# ft232h.net
KiCad netlist of a schematic drawn in Altium Designer
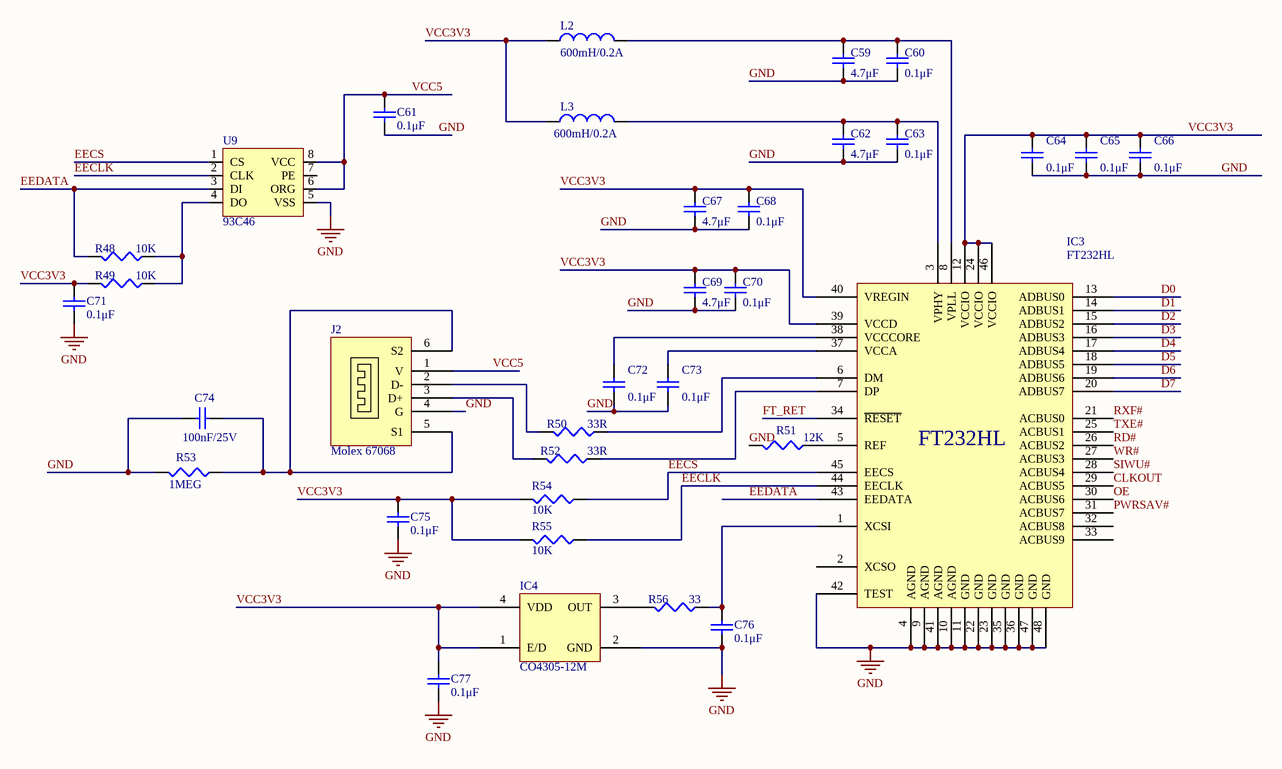
[diagram p0: ft232h.SchDoc]

(export (version "E")
  (design (tool "Eeschema 10.0.6"))
  (components
    (comp (ref "C59")
      (value "4.7μF")
      (footprint "1608[0603]")
      (description "Capacitor (Semiconductor SIM Model)")
      (fields (field (name "Comment") "Cap Semi") (field (name "PUBLISHER") "Altium Limited"))
      (libsource (lib "Miscellaneous Devices") (part "Cap Semi"))
    )
    (comp (ref "C60")
      (value "0.1μF")
      (footprint "1608[0603]")
      (description "Capacitor (Semiconductor SIM Model)")
      (fields (field (name "Comment") "Cap Semi") (field (name "PUBLISHER") "Altium Limited"))
      (libsource (lib "Miscellaneous Devices") (part "Cap Semi"))
    )
    (comp (ref "C61")
      (value "0.1μF")
      (footprint "1608[0603]")
      (description "Capacitor (Semiconductor SIM Model)")
      (fields (field (name "Comment") "Cap Semi") (field (name "PUBLISHER") "Altium Limited"))
      (libsource (lib "Miscellaneous Devices") (part "Cap Semi"))
    )
    (comp (ref "C62")
      (value "4.7μF")
      (footprint "1608[0603]")
      (description "Capacitor (Semiconductor SIM Model)")
      (fields (field (name "Comment") "Cap Semi") (field (name "PUBLISHER") "Altium Limited"))
      (libsource (lib "Miscellaneous Devices") (part "Cap Semi"))
    )
    (comp (ref "C63")
      (value "0.1μF")
      (footprint "1608[0603]")
      (description "Capacitor (Semiconductor SIM Model)")
      (fields (field (name "Comment") "Cap Semi") (field (name "PUBLISHER") "Altium Limited"))
      (libsource (lib "Miscellaneous Devices") (part "Cap Semi"))
    )
    (comp (ref "C64")
      (value "0.1μF")
      (footprint "1608[0603]")
      (description "Capacitor (Semiconductor SIM Model)")
      (fields (field (name "Comment") "Cap Semi") (field (name "PUBLISHER") "Altium Limited"))
      (libsource (lib "Miscellaneous Devices") (part "Cap Semi"))
    )
    (comp (ref "C65")
      (value "0.1μF")
      (footprint "1608[0603]")
      (description "Capacitor (Semiconductor SIM Model)")
      (fields (field (name "Comment") "Cap Semi") (field (name "PUBLISHER") "Altium Limited"))
      (libsource (lib "Miscellaneous Devices") (part "Cap Semi"))
    )
    (comp (ref "C66")
      (value "0.1μF")
      (footprint "1608[0603]")
      (description "Capacitor (Semiconductor SIM Model)")
      (fields (field (name "Comment") "Cap Semi") (field (name "PUBLISHER") "Altium Limited"))
      (libsource (lib "Miscellaneous Devices") (part "Cap Semi"))
    )
    (comp (ref "C67")
      (value "4.7μF")
      (footprint "1608[0603]")
      (description "Capacitor (Semiconductor SIM Model)")
      (fields (field (name "Comment") "Cap Semi") (field (name "PUBLISHER") "Altium Limited"))
      (libsource (lib "Miscellaneous Devices") (part "Cap Semi"))
    )
    (comp (ref "C68")
      (value "0.1μF")
      (footprint "1608[0603]")
      (description "Capacitor (Semiconductor SIM Model)")
      (fields (field (name "Comment") "Cap Semi") (field (name "PUBLISHER") "Altium Limited"))
      (libsource (lib "Miscellaneous Devices") (part "Cap Semi"))
    )
    (comp (ref "C69")
      (value "4.7μF")
      (footprint "1608[0603]")
      (description "Capacitor (Semiconductor SIM Model)")
      (fields (field (name "Comment") "Cap Semi") (field (name "PUBLISHER") "Altium Limited"))
      (libsource (lib "Miscellaneous Devices") (part "Cap Semi"))
    )
    (comp (ref "C70")
      (value "0.1μF")
      (footprint "1608[0603]")
      (description "Capacitor (Semiconductor SIM Model)")
      (fields (field (name "Comment") "Cap Semi") (field (name "PUBLISHER") "Altium Limited"))
      (libsource (lib "Miscellaneous Devices") (part "Cap Semi"))
    )
    (comp (ref "C71")
      (value "0.1μF")
      (footprint "1608[0603]")
      (description "Capacitor (Semiconductor SIM Model)")
      (fields (field (name "Comment") "Cap Semi") (field (name "PUBLISHER") "Altium Limited"))
      (libsource (lib "Miscellaneous Devices") (part "Cap Semi"))
    )
    (comp (ref "C72")
      (value "0.1μF")
      (footprint "1608[0603]")
      (description "Capacitor (Semiconductor SIM Model)")
      (fields (field (name "Comment") "Cap Semi") (field (name "PUBLISHER") "Altium Limited"))
      (libsource (lib "Miscellaneous Devices") (part "Cap Semi"))
    )
    (comp (ref "C73")
      (value "0.1μF")
      (footprint "1608[0603]")
      (description "Capacitor (Semiconductor SIM Model)")
      (fields (field (name "Comment") "Cap Semi") (field (name "PUBLISHER") "Altium Limited"))
      (libsource (lib "Miscellaneous Devices") (part "Cap Semi"))
    )
    (comp (ref "C74")
      (value "100nF/25V")
      (footprint "1608[0603]")
      (description "Capacitor (Semiconductor SIM Model)")
      (fields (field (name "Comment") "Cap Semi") (field (name "PUBLISHER") "Altium Limited"))
      (libsource (lib "Miscellaneous Devices") (part "Cap Semi"))
    )
    (comp (ref "C75")
      (value "0.1μF")
      (footprint "1608[0603]")
      (description "Capacitor (Semiconductor SIM Model)")
      (fields (field (name "Comment") "Cap Semi") (field (name "PUBLISHER") "Altium Limited"))
      (libsource (lib "Miscellaneous Devices") (part "Cap Semi"))
    )
    (comp (ref "C76")
      (value "0.1μF")
      (footprint "1608[0603]")
      (description "Capacitor (Semiconductor SIM Model)")
      (fields (field (name "Comment") "Cap Semi") (field (name "PUBLISHER") "Altium Limited"))
      (libsource (lib "Miscellaneous Devices") (part "Cap Semi"))
    )
    (comp (ref "C77")
      (value "0.1μF")
      (footprint "1608[0603]")
      (description "Capacitor (Semiconductor SIM Model)")
      (fields (field (name "Comment") "Cap Semi") (field (name "PUBLISHER") "Altium Limited"))
      (libsource (lib "Miscellaneous Devices") (part "Cap Semi"))
    )
    (comp (ref "IC3")
      (value "FT232HL")
      (footprint "FTDI Footprints:LQFP-48_L")
      (libsource (lib "nir_usb") (part "FT232HL"))
    )
    (comp (ref "IC4")
      (value "CO4305-12M")
      (footprint "CO4305-12")
      (libsource (lib "nir_usb") (part "CO4305-12M"))
    )
    (comp (ref "J2")
      (value "Molex 67068")
      (footprint "USB-A")
      (libsource (lib "nir_usb") (part "Molex 67068"))
    )
    (comp (ref "L2")
      (value "600mH/0.2A")
      (footprint "0603")
      (description "Inductor")
      (fields (field (name "PUBLISHER") "Altium Limited"))
      (libsource (lib "Miscellaneous Devices") (part "Inductor"))
    )
    (comp (ref "L3")
      (value "600mH/0.2A")
      (footprint "0603")
      (description "Inductor")
      (fields (field (name "PUBLISHER") "Altium Limited"))
      (libsource (lib "Miscellaneous Devices") (part "Inductor"))
    )
    (comp (ref "R48")
      (value "10K")
      (footprint "J1-0603")
      (description "Resistor")
      (fields (field (name "Comment") "Res3") (field (name "PUBLISHER") "Altium Limited"))
      (libsource (lib "Miscellaneous Devices") (part "Res3"))
    )
    (comp (ref "R49")
      (value "10K")
      (footprint "J1-0603")
      (description "Resistor")
      (fields (field (name "Comment") "Res3") (field (name "PUBLISHER") "Altium Limited"))
      (libsource (lib "Miscellaneous Devices") (part "Res3"))
    )
    (comp (ref "R50")
      (value "33R")
      (footprint "J1-0603")
      (description "Resistor")
      (fields (field (name "Comment") "Res3") (field (name "PUBLISHER") "Altium Limited"))
      (libsource (lib "Miscellaneous Devices") (part "Res3"))
    )
    (comp (ref "R51")
      (value "12K")
      (footprint "J1-0603")
      (description "Resistor")
      (fields (field (name "Comment") "Res3") (field (name "PUBLISHER") "Altium Limited"))
      (libsource (lib "Miscellaneous Devices") (part "Res3"))
    )
    (comp (ref "R52")
      (value "33R")
      (footprint "J1-0603")
      (description "Resistor")
      (fields (field (name "Comment") "Res3") (field (name "PUBLISHER") "Altium Limited"))
      (libsource (lib "Miscellaneous Devices") (part "Res3"))
    )
    (comp (ref "R53")
      (value "1MEG")
      (footprint "J1-0603")
      (description "Resistor")
      (fields (field (name "Comment") "Res3") (field (name "PUBLISHER") "Altium Limited"))
      (libsource (lib "Miscellaneous Devices") (part "Res3"))
    )
    (comp (ref "R54")
      (value "10K")
      (footprint "J1-0603")
      (description "Resistor")
      (fields (field (name "Comment") "Res3") (field (name "PUBLISHER") "Altium Limited"))
      (libsource (lib "Miscellaneous Devices") (part "Res3"))
    )
    (comp (ref "R55")
      (value "10K")
      (footprint "J1-0603")
      (description "Resistor")
      (fields (field (name "Comment") "Res3") (field (name "PUBLISHER") "Altium Limited"))
      (libsource (lib "Miscellaneous Devices") (part "Res3"))
    )
    (comp (ref "R56")
      (value "33")
      (footprint "J1-0603")
      (description "Resistor")
      (fields (field (name "Comment") "Res3") (field (name "PUBLISHER") "Altium Limited"))
      (libsource (lib "Miscellaneous Devices") (part "Res3"))
    )
    (comp (ref "U9")
      (value "93C46")
      (footprint "SOIC127P600X175-8N")
      (libsource (lib "nir_usb") (part "93C46"))
    )
  )
  (nets
    (net (code "1") (name "/CLKOUT") (class "Default")
      (node (ref "IC3") (pin "29") (pinfunction "ACBUS5_29") (pintype "passive"))
    )
    (net (code "2") (name "/D0") (class "Default")
      (node (ref "IC3") (pin "13") (pinfunction "ADBUS0_13") (pintype "passive"))
    )
    (net (code "3") (name "/D1") (class "Default")
      (node (ref "IC3") (pin "14") (pinfunction "ADBUS1_14") (pintype "passive"))
    )
    (net (code "4") (name "/D2") (class "Default")
      (node (ref "IC3") (pin "15") (pinfunction "ADBUS2_15") (pintype "passive"))
    )
    (net (code "5") (name "/D3") (class "Default")
      (node (ref "IC3") (pin "16") (pinfunction "ADBUS3_16") (pintype "passive"))
    )
    (net (code "6") (name "/D4") (class "Default")
      (node (ref "IC3") (pin "17") (pinfunction "ADBUS4_17") (pintype "passive"))
    )
    (net (code "7") (name "/D5") (class "Default")
      (node (ref "IC3") (pin "18") (pinfunction "ADBUS5_18") (pintype "passive"))
    )
    (net (code "8") (name "/D6") (class "Default")
      (node (ref "IC3") (pin "19") (pinfunction "ADBUS6_19") (pintype "passive"))
    )
    (net (code "9") (name "/D7") (class "Default")
      (node (ref "IC3") (pin "20") (pinfunction "ADBUS7_20") (pintype "passive"))
    )
    (net (code "10") (name "/EECLK") (class "Default")
      (node (ref "IC3") (pin "44") (pinfunction "EECLK_44") (pintype "passive"))
      (node (ref "R55") (pin "1") (pinfunction "1_1") (pintype "passive"))
      (node (ref "U9") (pin "2") (pinfunction "CLK_2") (pintype "passive"))
    )
    (net (code "11") (name "/EECS") (class "Default")
      (node (ref "IC3") (pin "45") (pinfunction "EECS_45") (pintype "passive"))
      (node (ref "R54") (pin "1") (pinfunction "1_1") (pintype "passive"))
      (node (ref "U9") (pin "1") (pinfunction "CS_1") (pintype "passive"))
    )
    (net (code "12") (name "/EEDATA") (class "Default")
      (node (ref "IC3") (pin "43") (pinfunction "EEDATA_43") (pintype "passive"))
      (node (ref "R48") (pin "2") (pinfunction "2_2") (pintype "passive"))
      (node (ref "U9") (pin "3") (pinfunction "DI_3") (pintype "passive"))
    )
    (net (code "13") (name "/FT_RET") (class "Default")
      (node (ref "IC3") (pin "34") (pinfunction "~{RESET}_34") (pintype "passive"))
    )
    (net (code "14") (name "/OE") (class "Default")
      (node (ref "IC3") (pin "30") (pinfunction "ACBUS6_30") (pintype "passive"))
    )
    (net (code "15") (name "/PWRSAV#") (class "Default")
      (node (ref "IC3") (pin "31") (pinfunction "ACBUS7_31") (pintype "passive"))
    )
    (net (code "16") (name "/RD#") (class "Default")
      (node (ref "IC3") (pin "26") (pinfunction "ACBUS2_26") (pintype "passive"))
    )
    (net (code "17") (name "/RXF#") (class "Default")
      (node (ref "IC3") (pin "21") (pinfunction "ACBUS0_21") (pintype "passive"))
    )
    (net (code "18") (name "/SIWU#") (class "Default")
      (node (ref "IC3") (pin "28") (pinfunction "ACBUS4_28") (pintype "passive"))
    )
    (net (code "19") (name "/TXE#") (class "Default")
      (node (ref "IC3") (pin "25") (pinfunction "ACBUS1_25") (pintype "passive"))
    )
    (net (code "20") (name "/VCC3V3") (class "Default")
      (node (ref "C64") (pin "2") (pinfunction "2_2") (pintype "passive"))
      (node (ref "C65") (pin "2") (pinfunction "2_2") (pintype "passive"))
      (node (ref "C66") (pin "2") (pinfunction "2_2") (pintype "passive"))
      (node (ref "C67") (pin "2") (pinfunction "2_2") (pintype "passive"))
      (node (ref "C68") (pin "2") (pinfunction "2_2") (pintype "passive"))
      (node (ref "C69") (pin "2") (pinfunction "2_2") (pintype "passive"))
      (node (ref "C70") (pin "2") (pinfunction "2_2") (pintype "passive"))
      (node (ref "C71") (pin "2") (pinfunction "2_2") (pintype "passive"))
      (node (ref "C75") (pin "2") (pinfunction "2_2") (pintype "passive"))
      (node (ref "C77") (pin "2") (pinfunction "2_2") (pintype "passive"))
      (node (ref "IC3") (pin "12") (pinfunction "VCCIO_12") (pintype "passive"))
      (node (ref "IC3") (pin "24") (pinfunction "VCCIO_24") (pintype "passive"))
      (node (ref "IC3") (pin "39") (pinfunction "VCCD_39") (pintype "passive"))
      (node (ref "IC3") (pin "40") (pinfunction "VREGIN_40") (pintype "passive"))
      (node (ref "IC3") (pin "46") (pinfunction "VCCIO_46") (pintype "passive"))
      (node (ref "IC4") (pin "1") (pinfunction "E/D_1") (pintype "passive"))
      (node (ref "IC4") (pin "4") (pinfunction "VDD_4") (pintype "passive"))
      (node (ref "L2") (pin "1") (pinfunction "1_1") (pintype "passive"))
      (node (ref "L3") (pin "1") (pinfunction "1_1") (pintype "passive"))
      (node (ref "R49") (pin "2") (pinfunction "2_2") (pintype "passive"))
      (node (ref "R54") (pin "2") (pinfunction "2_2") (pintype "passive"))
      (node (ref "R55") (pin "2") (pinfunction "2_2") (pintype "passive"))
    )
    (net (code "21") (name "/VCC5") (class "Default")
      (node (ref "C61") (pin "2") (pinfunction "2_2") (pintype "passive"))
      (node (ref "J2") (pin "1") (pinfunction "V_1") (pintype "passive"))
      (node (ref "U9") (pin "6") (pinfunction "ORG_6") (pintype "passive"))
      (node (ref "U9") (pin "8") (pinfunction "VCC_8") (pintype "passive"))
    )
    (net (code "22") (name "/WR#") (class "Default")
      (node (ref "IC3") (pin "27") (pinfunction "ACBUS3_27") (pintype "passive"))
    )
    (net (code "23") (name "GND") (class "Default")
      (node (ref "C59") (pin "1") (pinfunction "1_1") (pintype "passive"))
      (node (ref "C60") (pin "1") (pinfunction "1_1") (pintype "passive"))
      (node (ref "C61") (pin "1") (pinfunction "1_1") (pintype "passive"))
      (node (ref "C62") (pin "1") (pinfunction "1_1") (pintype "passive"))
      (node (ref "C63") (pin "1") (pinfunction "1_1") (pintype "passive"))
      (node (ref "C64") (pin "1") (pinfunction "1_1") (pintype "passive"))
      (node (ref "C65") (pin "1") (pinfunction "1_1") (pintype "passive"))
      (node (ref "C66") (pin "1") (pinfunction "1_1") (pintype "passive"))
      (node (ref "C67") (pin "1") (pinfunction "1_1") (pintype "passive"))
      (node (ref "C68") (pin "1") (pinfunction "1_1") (pintype "passive"))
      (node (ref "C69") (pin "1") (pinfunction "1_1") (pintype "passive"))
      (node (ref "C70") (pin "1") (pinfunction "1_1") (pintype "passive"))
      (node (ref "C71") (pin "1") (pinfunction "1_1") (pintype "passive"))
      (node (ref "C72") (pin "1") (pinfunction "1_1") (pintype "passive"))
      (node (ref "C73") (pin "1") (pinfunction "1_1") (pintype "passive"))
      (node (ref "C74") (pin "1") (pinfunction "1_1") (pintype "passive"))
      (node (ref "C75") (pin "1") (pinfunction "1_1") (pintype "passive"))
      (node (ref "C76") (pin "1") (pinfunction "1_1") (pintype "passive"))
      (node (ref "C77") (pin "1") (pinfunction "1_1") (pintype "passive"))
      (node (ref "IC3") (pin "10") (pinfunction "AGND_10") (pintype "passive"))
      (node (ref "IC3") (pin "11") (pinfunction "GND_11") (pintype "passive"))
      (node (ref "IC3") (pin "22") (pinfunction "GND_22") (pintype "passive"))
      (node (ref "IC3") (pin "23") (pinfunction "GND_23") (pintype "passive"))
      (node (ref "IC3") (pin "35") (pinfunction "GND_35") (pintype "passive"))
      (node (ref "IC3") (pin "36") (pinfunction "GND_36") (pintype "passive"))
      (node (ref "IC3") (pin "4") (pinfunction "AGND_4") (pintype "passive"))
      (node (ref "IC3") (pin "41") (pinfunction "AGND_41") (pintype "passive"))
      (node (ref "IC3") (pin "42") (pinfunction "TEST_42") (pintype "passive"))
      (node (ref "IC3") (pin "47") (pinfunction "GND_47") (pintype "passive"))
      (node (ref "IC3") (pin "48") (pinfunction "GND_48") (pintype "passive"))
      (node (ref "IC3") (pin "9") (pinfunction "AGND_9") (pintype "passive"))
      (node (ref "IC4") (pin "2") (pinfunction "GND_2") (pintype "passive"))
      (node (ref "J2") (pin "4") (pinfunction "G_4") (pintype "passive"))
      (node (ref "R51") (pin "2") (pinfunction "2_2") (pintype "passive"))
      (node (ref "R53") (pin "2") (pinfunction "2_2") (pintype "passive"))
      (node (ref "U9") (pin "5") (pinfunction "VSS_5") (pintype "passive"))
    )
    (net (code "24") (name "Net-(IC3-DM)") (class "Default")
      (node (ref "IC3") (pin "6") (pinfunction "DM_6") (pintype "passive"))
      (node (ref "R50") (pin "1") (pinfunction "1_1") (pintype "passive"))
    )
    (net (code "25") (name "Net-(IC3-DP)") (class "Default")
      (node (ref "IC3") (pin "7") (pinfunction "DP_7") (pintype "passive"))
      (node (ref "R52") (pin "1") (pinfunction "1_1") (pintype "passive"))
    )
    (net (code "26") (name "Net-(IC3-REF)") (class "Default")
      (node (ref "IC3") (pin "5") (pinfunction "REF_5") (pintype "passive"))
      (node (ref "R51") (pin "1") (pinfunction "1_1") (pintype "passive"))
    )
    (net (code "27") (name "Net-(IC3-VCCA)") (class "Default")
      (node (ref "C73") (pin "2") (pinfunction "2_2") (pintype "passive"))
      (node (ref "IC3") (pin "37") (pinfunction "VCCA_37") (pintype "passive"))
    )
    (net (code "28") (name "Net-(IC3-VCCCORE)") (class "Default")
      (node (ref "C72") (pin "2") (pinfunction "2_2") (pintype "passive"))
      (node (ref "IC3") (pin "38") (pinfunction "VCCCORE_38") (pintype "passive"))
    )
    (net (code "29") (name "Net-(IC3-VPHY)") (class "Default")
      (node (ref "C62") (pin "2") (pinfunction "2_2") (pintype "passive"))
      (node (ref "C63") (pin "2") (pinfunction "2_2") (pintype "passive"))
      (node (ref "IC3") (pin "3") (pinfunction "VPHY_3") (pintype "passive"))
      (node (ref "L3") (pin "2") (pinfunction "2_2") (pintype "passive"))
    )
    (net (code "30") (name "Net-(IC3-VPLL)") (class "Default")
      (node (ref "C59") (pin "2") (pinfunction "2_2") (pintype "passive"))
      (node (ref "C60") (pin "2") (pinfunction "2_2") (pintype "passive"))
      (node (ref "IC3") (pin "8") (pinfunction "VPLL_8") (pintype "passive"))
      (node (ref "L2") (pin "2") (pinfunction "2_2") (pintype "passive"))
    )
    (net (code "31") (name "Net-(IC3-XCSI)") (class "Default")
      (node (ref "C76") (pin "2") (pinfunction "2_2") (pintype "passive"))
      (node (ref "IC3") (pin "1") (pinfunction "XCSI_1") (pintype "passive"))
      (node (ref "R56") (pin "1") (pinfunction "1_1") (pintype "passive"))
    )
    (net (code "32") (name "Net-(IC4-OUT)") (class "Default")
      (node (ref "IC4") (pin "3") (pinfunction "OUT_3") (pintype "passive"))
      (node (ref "R56") (pin "2") (pinfunction "2_2") (pintype "passive"))
    )
    (net (code "33") (name "Net-(J2-D+)") (class "Default")
      (node (ref "J2") (pin "3") (pinfunction "D+_3") (pintype "passive"))
      (node (ref "R52") (pin "2") (pinfunction "2_2") (pintype "passive"))
    )
    (net (code "34") (name "Net-(J2-D-)") (class "Default")
      (node (ref "J2") (pin "2") (pinfunction "D-_2") (pintype "passive"))
      (node (ref "R50") (pin "2") (pinfunction "2_2") (pintype "passive"))
    )
    (net (code "35") (name "Net-(J2-S1)") (class "Default")
      (node (ref "C74") (pin "2") (pinfunction "2_2") (pintype "passive"))
      (node (ref "J2") (pin "5") (pinfunction "S1_5") (pintype "passive"))
      (node (ref "J2") (pin "6") (pinfunction "S2_6") (pintype "passive"))
      (node (ref "R53") (pin "1") (pinfunction "1_1") (pintype "passive"))
    )
    (net (code "36") (name "Net-(U9-DO)") (class "Default")
      (node (ref "R48") (pin "1") (pinfunction "1_1") (pintype "passive"))
      (node (ref "R49") (pin "1") (pinfunction "1_1") (pintype "passive"))
      (node (ref "U9") (pin "4") (pinfunction "DO_4") (pintype "passive"))
    )
    (net (code "37") (name "unconnected-(IC3-ACBUS8-Pad32)") (class "Default")
      (node (ref "IC3") (pin "32") (pinfunction "ACBUS8_32") (pintype "passive"))
    )
    (net (code "38") (name "unconnected-(IC3-ACBUS9-Pad33)") (class "Default")
      (node (ref "IC3") (pin "33") (pinfunction "ACBUS9_33") (pintype "passive"))
    )
    (net (code "39") (name "unconnected-(IC3-XCSO-Pad2)") (class "Default")
      (node (ref "IC3") (pin "2") (pinfunction "XCSO_2") (pintype "passive"))
    )
    (net (code "40") (name "unconnected-(U9-PE-Pad7)") (class "Default")
      (node (ref "U9") (pin "7") (pinfunction "PE_7") (pintype "passive"))
    )
  )
)
